# BaseBoard.net
KiCad netlist of a schematic drawn in EAGLE
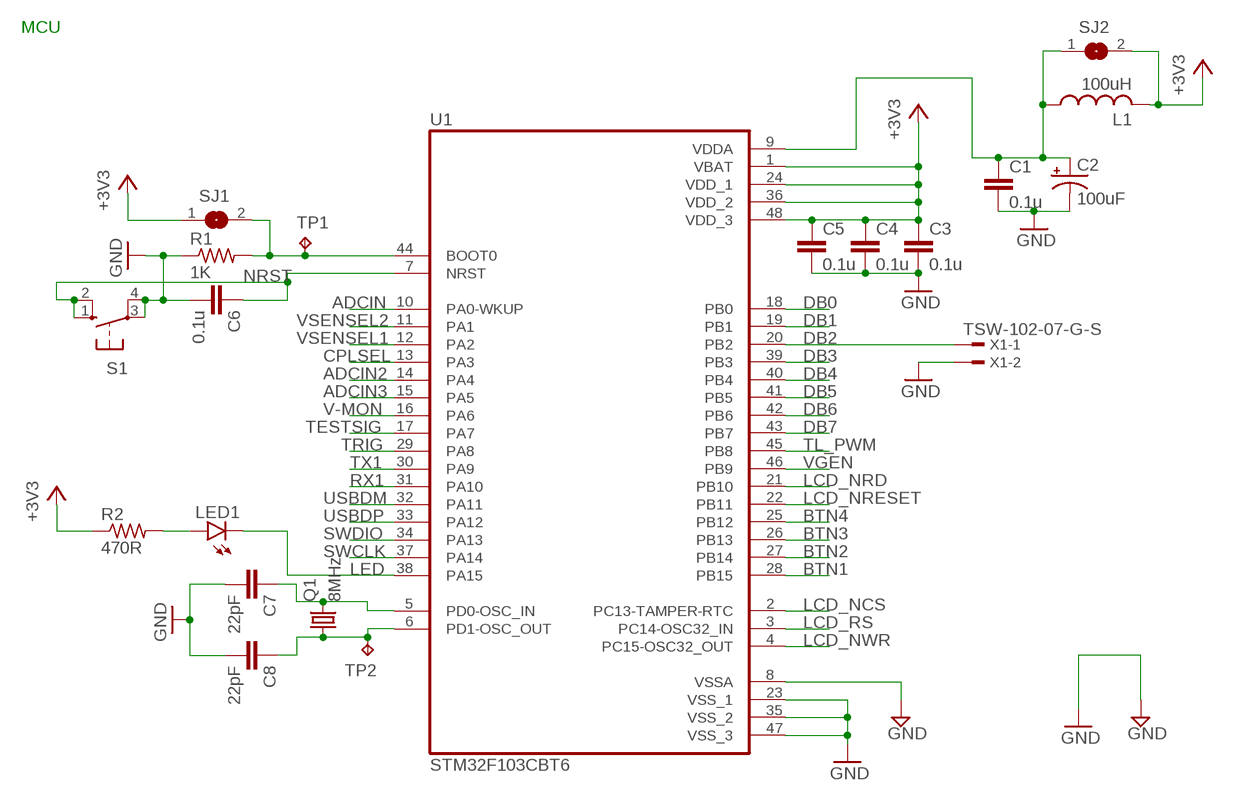
[diagram p0: schematic, sheet 1]
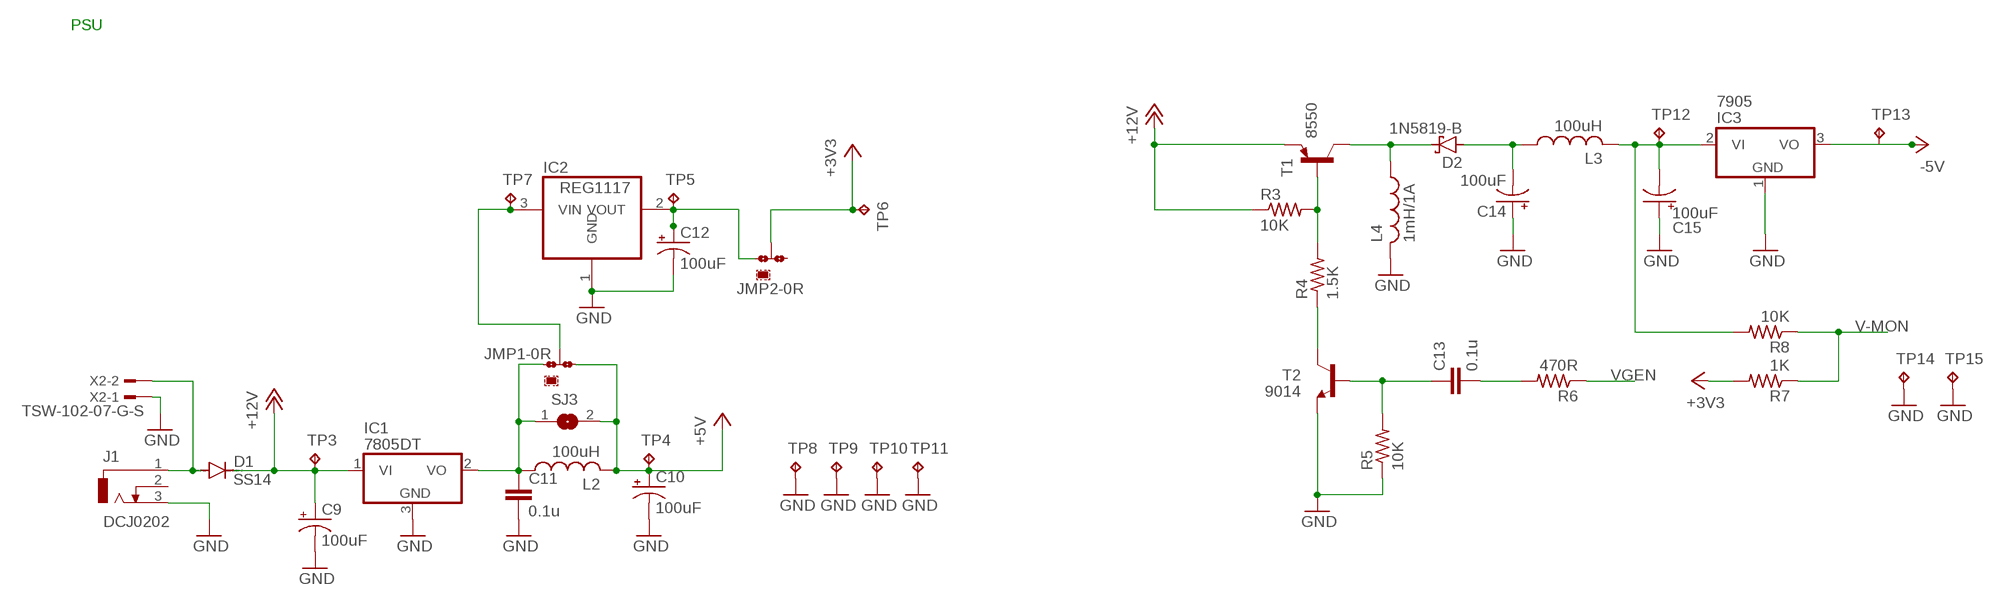
[diagram p1: schematic, sheet 2]
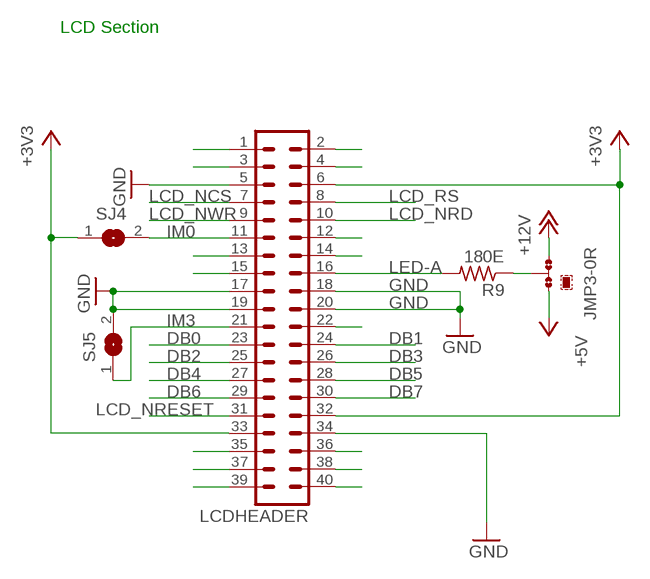
[diagram p2: schematic, sheet 3]
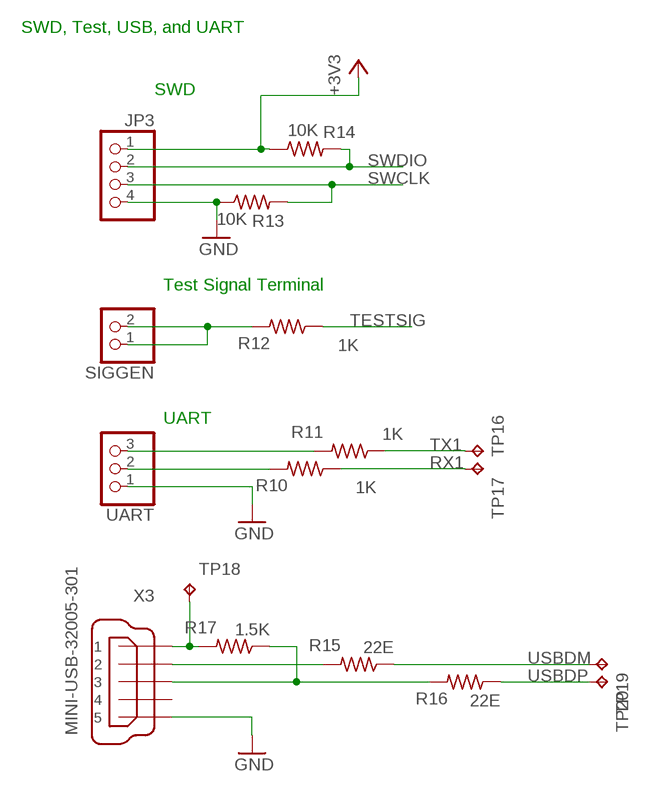
[diagram p3: schematic, sheet 4]
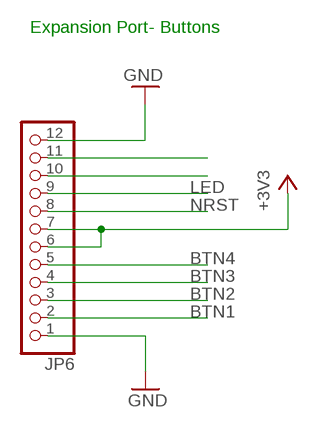
[diagram p4: schematic, sheet 5]
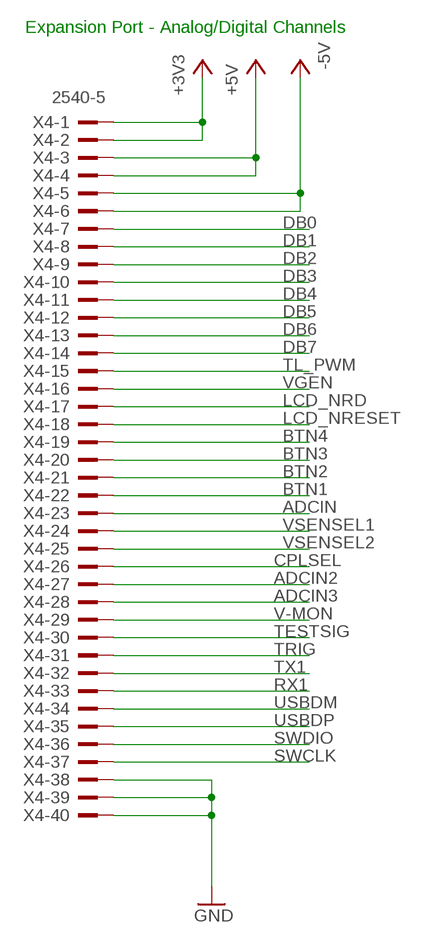
[diagram p5: schematic, sheet 6]

(export (version "E")
  (design (tool "Eeschema 10.0.6"))
  (components
    (comp (ref "X4")
      (value "2540-5")
      (footprint "eagle-import:PAK100_2500-5-40")
      (libsource (lib "eagle-import") (part "2540-5"))
    )
    (comp (ref "C1")
      (value "0.1u")
      (footprint "eagle-import:C1206")
      (libsource (lib "eagle-import") (part "C-EUC1206"))
    )
    (comp (ref "C2")
      (value "100uF")
      (footprint "eagle-import:CT6032")
      (libsource (lib "eagle-import") (part "CPOL-USCT6032"))
    )
    (comp (ref "C3")
      (value "0.1u")
      (footprint "eagle-import:C1206")
      (libsource (lib "eagle-import") (part "C-EUC1206"))
    )
    (comp (ref "C4")
      (value "0.1u")
      (footprint "eagle-import:C1206")
      (libsource (lib "eagle-import") (part "C-EUC1206"))
    )
    (comp (ref "C5")
      (value "0.1u")
      (footprint "eagle-import:C1206")
      (libsource (lib "eagle-import") (part "C-EUC1206"))
    )
    (comp (ref "C6")
      (value "0.1u")
      (footprint "eagle-import:C1206")
      (libsource (lib "eagle-import") (part "C-EUC1206"))
    )
    (comp (ref "C7")
      (value "22pF")
      (footprint "eagle-import:C1206")
      (libsource (lib "eagle-import") (part "C-EUC1206"))
    )
    (comp (ref "C8")
      (value "22pF")
      (footprint "eagle-import:C1206")
      (libsource (lib "eagle-import") (part "C-EUC1206"))
    )
    (comp (ref "L1")
      (value "100uH")
      (footprint "eagle-import:0204_5")
      (libsource (lib "eagle-import") (part "L-US0204/5"))
    )
    (comp (ref "LED1")
      (value "LEDCHIPLED_1206")
      (footprint "eagle-import:CHIPLED_1206")
      (libsource (lib "eagle-import") (part "LEDCHIPLED_1206"))
    )
    (comp (ref "Q1")
      (value "8MHz")
      (footprint "eagle-import:HC49_S")
      (libsource (lib "eagle-import") (part "CRYSTALHC49S"))
    )
    (comp (ref "R1")
      (value "1K")
      (footprint "eagle-import:R0805")
      (libsource (lib "eagle-import") (part "R-US_R0805"))
    )
    (comp (ref "R2")
      (value "470R")
      (footprint "eagle-import:R0805")
      (libsource (lib "eagle-import") (part "R-US_R0805"))
    )
    (comp (ref "S1")
      (value "10-XX")
      (footprint "eagle-import:B3F-10XX")
      (fields (field (name "MPN") "B3F-1000"))
      (libsource (lib "eagle-import") (part "10-XX"))
    )
    (comp (ref "SJ1")
      (value "SJW")
      (footprint "eagle-import:SJW")
      (libsource (lib "eagle-import") (part "SJW"))
    )
    (comp (ref "SJ2")
      (value "SJW")
      (footprint "eagle-import:SJW")
      (libsource (lib "eagle-import") (part "SJW"))
    )
    (comp (ref "TP1")
      (value "TPB1,27")
      (footprint "eagle-import:B1,27")
      (libsource (lib "eagle-import") (part "TPB1,27"))
    )
    (comp (ref "TP2")
      (value "TPB1,27")
      (footprint "eagle-import:B1,27")
      (libsource (lib "eagle-import") (part "TPB1,27"))
    )
    (comp (ref "U1")
      (value "STM32F103CBT6")
      (footprint "eagle-import:QFP50P900X900X160-48N")
      (fields (field (name "MF") "STMicroelectronics"))
      (libsource (lib "eagle-import") (part "STM32F103CBT6"))
    )
    (comp (ref "X1")
      (value "TSW-102-07-G-S")
      (footprint "eagle-import:TSW-102-XX-G-S")
      (fields (field (name "MF") "Samtec Inc."))
      (libsource (lib "eagle-import") (part "TSW-102--G-S07"))
    )
    (comp (ref "C9")
      (value "100uF")
      (footprint "eagle-import:CT6032")
      (libsource (lib "eagle-import") (part "CPOL-USCT6032"))
    )
    (comp (ref "C10")
      (value "100uF")
      (footprint "eagle-import:CT6032")
      (libsource (lib "eagle-import") (part "CPOL-USCT6032"))
    )
    (comp (ref "C11")
      (value "0.1u")
      (footprint "eagle-import:C1206")
      (libsource (lib "eagle-import") (part "C-EUC1206"))
    )
    (comp (ref "C12")
      (value "100uF")
      (footprint "eagle-import:CT6032")
      (libsource (lib "eagle-import") (part "CPOL-USCT6032"))
    )
    (comp (ref "C13")
      (value "0.1u")
      (footprint "eagle-import:C1206")
      (libsource (lib "eagle-import") (part "C-EUC1206"))
    )
    (comp (ref "C14")
      (value "100uF")
      (footprint "eagle-import:CT6032")
      (libsource (lib "eagle-import") (part "CPOL-USCT6032"))
    )
    (comp (ref "C15")
      (value "100uF")
      (footprint "eagle-import:CT6032")
      (libsource (lib "eagle-import") (part "CPOL-USCT6032"))
    )
    (comp (ref "D1")
      (value "SS14")
      (footprint "eagle-import:SMB")
      (libsource (lib "eagle-import") (part "ES2D"))
    )
    (comp (ref "D2")
      (value "1N5819-B")
      (footprint "eagle-import:DO41-7.6")
      (libsource (lib "eagle-import") (part "1N5819-B"))
    )
    (comp (ref "IC1")
      (value "7805DT")
      (footprint "eagle-import:TO252")
      (libsource (lib "eagle-import") (part "78DT05"))
    )
    (comp (ref "IC2")
      (value "REG1117")
      (footprint "eagle-import:SOT223")
      (libsource (lib "eagle-import") (part "REG1117"))
    )
    (comp (ref "IC3")
      (value "7905")
      (footprint "eagle-import:TO92")
      (libsource (lib "eagle-import") (part "79ZL05"))
    )
    (comp (ref "J1")
      (value "DCJ0202")
      (footprint "eagle-import:DCJ0202")
      (libsource (lib "eagle-import") (part "DCJ0202"))
    )
    (comp (ref "JMP1")
      (value "0R-JUMPA")
      (footprint "eagle-import:A0R-JMP")
      (libsource (lib "eagle-import") (part "0R-JUMPA"))
    )
    (comp (ref "JMP2")
      (value "0R-JUMPA")
      (footprint "eagle-import:A0R-JMP")
      (libsource (lib "eagle-import") (part "0R-JUMPA"))
    )
    (comp (ref "L2")
      (value "100uH")
      (footprint "eagle-import:0204_5")
      (libsource (lib "eagle-import") (part "L-US0204/5"))
    )
    (comp (ref "L3")
      (value "100uH")
      (footprint "eagle-import:0204_5")
      (libsource (lib "eagle-import") (part "L-US0204/5"))
    )
    (comp (ref "L4")
      (value "1mH/1A")
      (footprint "eagle-import:6000-XXXX-RC")
      (libsource (lib "eagle-import") (part "L-US6000-XXX-RC"))
    )
    (comp (ref "R3")
      (value "10K")
      (footprint "eagle-import:R0805")
      (libsource (lib "eagle-import") (part "R-US_R0805"))
    )
    (comp (ref "R4")
      (value "1.5K")
      (footprint "eagle-import:R0805")
      (libsource (lib "eagle-import") (part "R-US_R0805"))
    )
    (comp (ref "R5")
      (value "10K")
      (footprint "eagle-import:R0805")
      (libsource (lib "eagle-import") (part "R-US_R0805"))
    )
    (comp (ref "R6")
      (value "470R")
      (footprint "eagle-import:R0805")
      (libsource (lib "eagle-import") (part "R-US_R0805"))
    )
    (comp (ref "R7")
      (value "1K")
      (footprint "eagle-import:R0805")
      (libsource (lib "eagle-import") (part "R-US_R0805"))
    )
    (comp (ref "R8")
      (value "10K")
      (footprint "eagle-import:R0805")
      (libsource (lib "eagle-import") (part "R-US_R0805"))
    )
    (comp (ref "SJ3")
      (value "SJW")
      (footprint "eagle-import:SJW")
      (libsource (lib "eagle-import") (part "SJW"))
    )
    (comp (ref "T1")
      (value "8550")
      (footprint "eagle-import:TO92")
      (libsource (lib "eagle-import") (part "-PNP-TO92"))
    )
    (comp (ref "T2")
      (value "9014")
      (footprint "eagle-import:TO92")
      (libsource (lib "eagle-import") (part "-NPN-TO92"))
    )
    (comp (ref "TP3")
      (value "TPB1,27")
      (footprint "eagle-import:B1,27")
      (libsource (lib "eagle-import") (part "TPB1,27"))
    )
    (comp (ref "TP4")
      (value "TPB1,27")
      (footprint "eagle-import:B1,27")
      (libsource (lib "eagle-import") (part "TPB1,27"))
    )
    (comp (ref "TP5")
      (value "TPB1,27")
      (footprint "eagle-import:B1,27")
      (libsource (lib "eagle-import") (part "TPB1,27"))
    )
    (comp (ref "TP6")
      (value "TPB1,27")
      (footprint "eagle-import:B1,27")
      (libsource (lib "eagle-import") (part "TPB1,27"))
    )
    (comp (ref "TP7")
      (value "TPB1,27")
      (footprint "eagle-import:B1,27")
      (libsource (lib "eagle-import") (part "TPB1,27"))
    )
    (comp (ref "TP8")
      (value "TPB1,27")
      (footprint "eagle-import:B1,27")
      (libsource (lib "eagle-import") (part "TPB1,27"))
    )
    (comp (ref "TP9")
      (value "TPB1,27")
      (footprint "eagle-import:B1,27")
      (libsource (lib "eagle-import") (part "TPB1,27"))
    )
    (comp (ref "TP10")
      (value "TPB1,27")
      (footprint "eagle-import:B1,27")
      (libsource (lib "eagle-import") (part "TPB1,27"))
    )
    (comp (ref "TP11")
      (value "TPB1,27")
      (footprint "eagle-import:B1,27")
      (libsource (lib "eagle-import") (part "TPB1,27"))
    )
    (comp (ref "TP12")
      (value "TPB1,27")
      (footprint "eagle-import:B1,27")
      (libsource (lib "eagle-import") (part "TPB1,27"))
    )
    (comp (ref "TP13")
      (value "TPB1,27")
      (footprint "eagle-import:B1,27")
      (libsource (lib "eagle-import") (part "TPB1,27"))
    )
    (comp (ref "TP14")
      (value "TPB1,27")
      (footprint "eagle-import:B1,27")
      (libsource (lib "eagle-import") (part "TPB1,27"))
    )
    (comp (ref "TP15")
      (value "TPB1,27")
      (footprint "eagle-import:B1,27")
      (libsource (lib "eagle-import") (part "TPB1,27"))
    )
    (comp (ref "X2")
      (value "TSW-102-07-G-S")
      (footprint "eagle-import:TSW-102-XX-G-S")
      (fields (field (name "MF") "Samtec Inc."))
      (libsource (lib "eagle-import") (part "TSW-102--G-S07"))
    )
    (comp (ref "JMP3")
      (value "0R-JUMPA")
      (footprint "eagle-import:A0R-JMP")
      (libsource (lib "eagle-import") (part "0R-JUMPA"))
    )
    (comp (ref "LCDHEADER")
      (value "MA20-2")
      (footprint "eagle-import:MA20-2")
      (libsource (lib "eagle-import") (part "MA20-2"))
    )
    (comp (ref "R9")
      (value "180E")
      (footprint "eagle-import:R0805")
      (libsource (lib "eagle-import") (part "R-US_R0805"))
    )
    (comp (ref "SJ4") (value "SJ") (footprint "eagle-import:SJ") (libsource (lib "eagle-import") (part "SJ")))
    (comp (ref "SJ5") (value "SJ") (footprint "eagle-import:SJ") (libsource (lib "eagle-import") (part "SJ")))
    (comp (ref "JP3")
      (value "PINHD-1X4")
      (footprint "eagle-import:1X04")
      (libsource (lib "eagle-import") (part "PINHD-1X4"))
    )
    (comp (ref "R10")
      (value "1K")
      (footprint "eagle-import:R0805")
      (libsource (lib "eagle-import") (part "R-US_R0805"))
    )
    (comp (ref "R11")
      (value "1K")
      (footprint "eagle-import:R0805")
      (libsource (lib "eagle-import") (part "R-US_R0805"))
    )
    (comp (ref "R12")
      (value "1K")
      (footprint "eagle-import:R0805")
      (libsource (lib "eagle-import") (part "R-US_R0805"))
    )
    (comp (ref "R13")
      (value "10K")
      (footprint "eagle-import:R0805")
      (libsource (lib "eagle-import") (part "R-US_R0805"))
    )
    (comp (ref "R14")
      (value "10K")
      (footprint "eagle-import:R0805")
      (libsource (lib "eagle-import") (part "R-US_R0805"))
    )
    (comp (ref "R15")
      (value "22E")
      (footprint "eagle-import:R0805")
      (libsource (lib "eagle-import") (part "R-US_R0805"))
    )
    (comp (ref "R16")
      (value "22E")
      (footprint "eagle-import:R0805")
      (libsource (lib "eagle-import") (part "R-US_R0805"))
    )
    (comp (ref "R17")
      (value "1.5K")
      (footprint "eagle-import:R0805")
      (libsource (lib "eagle-import") (part "R-US_R0805"))
    )
    (comp (ref "SIGGEN")
      (value "PINHD-1X2")
      (footprint "eagle-import:1X02")
      (libsource (lib "eagle-import") (part "PINHD-1X2"))
    )
    (comp (ref "TP16")
      (value "TPB1,27")
      (footprint "eagle-import:B1,27")
      (libsource (lib "eagle-import") (part "TPB1,27"))
    )
    (comp (ref "TP17")
      (value "TPB1,27")
      (footprint "eagle-import:B1,27")
      (libsource (lib "eagle-import") (part "TPB1,27"))
    )
    (comp (ref "TP18")
      (value "TPB1,27")
      (footprint "eagle-import:B1,27")
      (libsource (lib "eagle-import") (part "TPB1,27"))
    )
    (comp (ref "TP19")
      (value "TPB1,27")
      (footprint "eagle-import:B1,27")
      (libsource (lib "eagle-import") (part "TPB1,27"))
    )
    (comp (ref "TP20")
      (value "TPB1,27")
      (footprint "eagle-import:B1,27")
      (libsource (lib "eagle-import") (part "TPB1,27"))
    )
    (comp (ref "UART")
      (value "PINHD-1X3")
      (footprint "eagle-import:1X03")
      (libsource (lib "eagle-import") (part "PINHD-1X3"))
    )
    (comp (ref "X3")
      (value "MINI-USB-32005-301")
      (footprint "eagle-import:32005-301")
      (libsource (lib "eagle-import") (part "MINI-USB-32005-301"))
    )
    (comp (ref "JP6")
      (value "PINHD-1X12")
      (footprint "eagle-import:1X12")
      (libsource (lib "eagle-import") (part "PINHD-1X12"))
    )
  )
  (nets
    (net (code "1") (name "+3V3") (class "Default")
      (node (ref "C3") (pin "1") (pinfunction "1_1") (pintype "passive"))
      (node (ref "C4") (pin "1") (pinfunction "1_1") (pintype "passive"))
      (node (ref "C5") (pin "1") (pinfunction "1_1") (pintype "passive"))
      (node (ref "JMP2") (pin "2") (pinfunction "2_2") (pintype "passive"))
      (node (ref "JP3") (pin "1") (pinfunction "1_1") (pintype "passive"))
      (node (ref "JP6") (pin "6") (pinfunction "6_6") (pintype "passive"))
      (node (ref "JP6") (pin "7") (pinfunction "7_7") (pintype "passive"))
      (node (ref "L1") (pin "2") (pinfunction "2_2") (pintype "passive"))
      (node (ref "LCDHEADER") (pin "32") (pinfunction "32_32") (pintype "passive"))
      (node (ref "LCDHEADER") (pin "33") (pinfunction "33_33") (pintype "passive"))
      (node (ref "LCDHEADER") (pin "6") (pinfunction "6_6") (pintype "passive"))
      (node (ref "R14") (pin "1") (pinfunction "1_1") (pintype "passive"))
      (node (ref "R2") (pin "1") (pinfunction "1_1") (pintype "passive"))
      (node (ref "R7") (pin "2") (pinfunction "2_2") (pintype "passive"))
      (node (ref "SJ1") (pin "1") (pinfunction "1_1") (pintype "passive"))
      (node (ref "SJ2") (pin "2") (pinfunction "2_2") (pintype "passive"))
      (node (ref "SJ4") (pin "1") (pinfunction "1_1") (pintype "passive"))
      (node (ref "TP6") (pin "TP") (pinfunction "TP_TP") (pintype "input"))
      (node (ref "U1") (pin "1") (pinfunction "VBAT_1") (pintype "power_in"))
      (node (ref "U1") (pin "24") (pinfunction "VDD_1_24") (pintype "power_in"))
      (node (ref "U1") (pin "36") (pinfunction "VDD_2_36") (pintype "power_in"))
      (node (ref "U1") (pin "48") (pinfunction "VDD_3_48") (pintype "power_in"))
      (node (ref "X4") (pin "1") (pinfunction "KL_1") (pintype "passive"))
      (node (ref "X4") (pin "2") (pinfunction "KL_2") (pintype "passive"))
    )
    (net (code "2") (name "+5V") (class "Default")
      (node (ref "C10") (pin "+") (pinfunction "+_+") (pintype "passive"))
      (node (ref "JMP1") (pin "3") (pinfunction "3_3") (pintype "passive"))
      (node (ref "JMP3") (pin "1") (pinfunction "1_1") (pintype "passive"))
      (node (ref "L2") (pin "2") (pinfunction "2_2") (pintype "passive"))
      (node (ref "SJ3") (pin "2") (pinfunction "2_2") (pintype "passive"))
      (node (ref "TP4") (pin "TP") (pinfunction "TP_TP") (pintype "input"))
      (node (ref "X4") (pin "3") (pinfunction "KL_3") (pintype "passive"))
      (node (ref "X4") (pin "4") (pinfunction "KL_4") (pintype "passive"))
    )
    (net (code "3") (name "+12V") (class "Default")
      (node (ref "C9") (pin "+") (pinfunction "+_+") (pintype "passive"))
      (node (ref "D1") (pin "C") (pinfunction "C_C") (pintype "passive"))
      (node (ref "IC1") (pin "1") (pinfunction "VI_1") (pintype "input"))
      (node (ref "JMP3") (pin "3") (pinfunction "3_3") (pintype "passive"))
      (node (ref "R3") (pin "1") (pinfunction "1_1") (pintype "passive"))
      (node (ref "T1") (pin "1") (pinfunction "E_1") (pintype "passive"))
      (node (ref "TP3") (pin "TP") (pinfunction "TP_TP") (pintype "input"))
    )
    (net (code "4") (name "-5V") (class "Default")
      (node (ref "IC3") (pin "3") (pinfunction "VO_3") (pintype "passive"))
      (node (ref "TP13") (pin "TP") (pinfunction "TP_TP") (pintype "input"))
      (node (ref "X4") (pin "5") (pinfunction "KL_5") (pintype "passive"))
      (node (ref "X4") (pin "6") (pinfunction "KL_6") (pintype "passive"))
    )
    (net (code "5") (name "ADCIN") (class "Default")
      (node (ref "U1") (pin "10") (pinfunction "PA0-WKUP_10") (pintype "bidirectional"))
      (node (ref "X4") (pin "23") (pinfunction "KL_23") (pintype "passive"))
    )
    (net (code "6") (name "ADCIN2") (class "Default")
      (node (ref "U1") (pin "14") (pinfunction "PA4_14") (pintype "bidirectional"))
      (node (ref "X4") (pin "27") (pinfunction "KL_27") (pintype "passive"))
    )
    (net (code "7") (name "ADCIN3") (class "Default")
      (node (ref "U1") (pin "15") (pinfunction "PA5_15") (pintype "bidirectional"))
      (node (ref "X4") (pin "28") (pinfunction "KL_28") (pintype "passive"))
    )
    (net (code "8") (name "BTN1") (class "Default")
      (node (ref "JP6") (pin "2") (pinfunction "2_2") (pintype "passive"))
      (node (ref "U1") (pin "28") (pinfunction "PB15_28") (pintype "bidirectional"))
      (node (ref "X4") (pin "22") (pinfunction "KL_22") (pintype "passive"))
    )
    (net (code "9") (name "BTN2") (class "Default")
      (node (ref "JP6") (pin "3") (pinfunction "3_3") (pintype "passive"))
      (node (ref "U1") (pin "27") (pinfunction "PB14_27") (pintype "bidirectional"))
      (node (ref "X4") (pin "21") (pinfunction "KL_21") (pintype "passive"))
    )
    (net (code "10") (name "BTN3") (class "Default")
      (node (ref "JP6") (pin "4") (pinfunction "4_4") (pintype "passive"))
      (node (ref "U1") (pin "26") (pinfunction "PB13_26") (pintype "bidirectional"))
      (node (ref "X4") (pin "20") (pinfunction "KL_20") (pintype "passive"))
    )
    (net (code "11") (name "BTN4") (class "Default")
      (node (ref "JP6") (pin "5") (pinfunction "5_5") (pintype "passive"))
      (node (ref "U1") (pin "25") (pinfunction "PB12_25") (pintype "bidirectional"))
      (node (ref "X4") (pin "19") (pinfunction "KL_19") (pintype "passive"))
    )
    (net (code "12") (name "CPLSEL") (class "Default")
      (node (ref "U1") (pin "13") (pinfunction "PA3_13") (pintype "bidirectional"))
      (node (ref "X4") (pin "26") (pinfunction "KL_26") (pintype "passive"))
    )
    (net (code "13") (name "DB0") (class "Default")
      (node (ref "LCDHEADER") (pin "23") (pinfunction "23_23") (pintype "passive"))
      (node (ref "U1") (pin "18") (pinfunction "PB0_18") (pintype "bidirectional"))
      (node (ref "X4") (pin "7") (pinfunction "KL_7") (pintype "passive"))
    )
    (net (code "14") (name "DB1") (class "Default")
      (node (ref "LCDHEADER") (pin "24") (pinfunction "24_24") (pintype "passive"))
      (node (ref "U1") (pin "19") (pinfunction "PB1_19") (pintype "bidirectional"))
      (node (ref "X4") (pin "8") (pinfunction "KL_8") (pintype "passive"))
    )
    (net (code "15") (name "DB2") (class "Default")
      (node (ref "LCDHEADER") (pin "25") (pinfunction "25_25") (pintype "passive"))
      (node (ref "U1") (pin "20") (pinfunction "PB2_20") (pintype "bidirectional"))
      (node (ref "X1") (pin "1") (pinfunction "1_1") (pintype "passive"))
      (node (ref "X4") (pin "9") (pinfunction "KL_9") (pintype "passive"))
    )
    (net (code "16") (name "DB3") (class "Default")
      (node (ref "LCDHEADER") (pin "26") (pinfunction "26_26") (pintype "passive"))
      (node (ref "U1") (pin "39") (pinfunction "PB3_39") (pintype "bidirectional"))
      (node (ref "X4") (pin "10") (pinfunction "KL_10") (pintype "passive"))
    )
    (net (code "17") (name "DB4") (class "Default")
      (node (ref "LCDHEADER") (pin "27") (pinfunction "27_27") (pintype "passive"))
      (node (ref "U1") (pin "40") (pinfunction "PB4_40") (pintype "bidirectional"))
      (node (ref "X4") (pin "11") (pinfunction "KL_11") (pintype "passive"))
    )
    (net (code "18") (name "DB5") (class "Default")
      (node (ref "LCDHEADER") (pin "28") (pinfunction "28_28") (pintype "passive"))
      (node (ref "U1") (pin "41") (pinfunction "PB5_41") (pintype "bidirectional"))
      (node (ref "X4") (pin "12") (pinfunction "KL_12") (pintype "passive"))
    )
    (net (code "19") (name "DB6") (class "Default")
      (node (ref "LCDHEADER") (pin "29") (pinfunction "29_29") (pintype "passive"))
      (node (ref "U1") (pin "42") (pinfunction "PB6_42") (pintype "bidirectional"))
      (node (ref "X4") (pin "13") (pinfunction "KL_13") (pintype "passive"))
    )
    (net (code "20") (name "DB7") (class "Default")
      (node (ref "LCDHEADER") (pin "30") (pinfunction "30_30") (pintype "passive"))
      (node (ref "U1") (pin "43") (pinfunction "PB7_43") (pintype "bidirectional"))
      (node (ref "X4") (pin "14") (pinfunction "KL_14") (pintype "passive"))
    )
    (net (code "21") (name "GND") (class "Default")
      (node (ref "C1") (pin "2") (pinfunction "2_2") (pintype "passive"))
      (node (ref "C10") (pin "-") (pinfunction "-_-") (pintype "passive"))
      (node (ref "C11") (pin "2") (pinfunction "2_2") (pintype "passive"))
      (node (ref "C12") (pin "-") (pinfunction "-_-") (pintype "passive"))
      (node (ref "C14") (pin "+") (pinfunction "+_+") (pintype "passive"))
      (node (ref "C15") (pin "+") (pinfunction "+_+") (pintype "passive"))
      (node (ref "C2") (pin "-") (pinfunction "-_-") (pintype "passive"))
      (node (ref "C3") (pin "2") (pinfunction "2_2") (pintype "passive"))
      (node (ref "C4") (pin "2") (pinfunction "2_2") (pintype "passive"))
      (node (ref "C5") (pin "2") (pinfunction "2_2") (pintype "passive"))
      (node (ref "C6") (pin "2") (pinfunction "2_2") (pintype "passive"))
      (node (ref "C7") (pin "2") (pinfunction "2_2") (pintype "passive"))
      (node (ref "C8") (pin "2") (pinfunction "2_2") (pintype "passive"))
      (node (ref "C9") (pin "-") (pinfunction "-_-") (pintype "passive"))
      (node (ref "IC1") (pin "3") (pinfunction "GND_3") (pintype "passive"))
      (node (ref "IC2") (pin "1") (pinfunction "GND_1") (pintype "power_in"))
      (node (ref "IC3") (pin "1") (pinfunction "GND_1") (pintype "passive"))
      (node (ref "J1") (pin "3") (pinfunction "3_3") (pintype "passive"))
      (node (ref "JP3") (pin "4") (pinfunction "4_4") (pintype "passive"))
      (node (ref "JP6") (pin "1") (pinfunction "1_1") (pintype "passive"))
      (node (ref "JP6") (pin "12") (pinfunction "12_12") (pintype "passive"))
      (node (ref "L4") (pin "2") (pinfunction "2_2") (pintype "passive"))
      (node (ref "LCDHEADER") (pin "17") (pinfunction "17_17") (pintype "passive"))
      (node (ref "LCDHEADER") (pin "18") (pinfunction "18_18") (pintype "passive"))
      (node (ref "LCDHEADER") (pin "19") (pinfunction "19_19") (pintype "passive"))
      (node (ref "LCDHEADER") (pin "20") (pinfunction "20_20") (pintype "passive"))
      (node (ref "LCDHEADER") (pin "34") (pinfunction "34_34") (pintype "passive"))
      (node (ref "LCDHEADER") (pin "5") (pinfunction "5_5") (pintype "passive"))
      (node (ref "R1") (pin "1") (pinfunction "1_1") (pintype "passive"))
      (node (ref "R13") (pin "1") (pinfunction "1_1") (pintype "passive"))
      (node (ref "R5") (pin "1") (pinfunction "1_1") (pintype "passive"))
      (node (ref "S1") (pin "3") (pinfunction "P_3") (pintype "passive"))
      (node (ref "S1") (pin "4") (pinfunction "P1_4") (pintype "passive"))
      (node (ref "SJ5") (pin "2") (pinfunction "2_2") (pintype "passive"))
      (node (ref "T2") (pin "1") (pinfunction "E_1") (pintype "passive"))
      (node (ref "TP10") (pin "TP") (pinfunction "TP_TP") (pintype "input"))
      (node (ref "TP11") (pin "TP") (pinfunction "TP_TP") (pintype "input"))
      (node (ref "TP14") (pin "TP") (pinfunction "TP_TP") (pintype "input"))
      (node (ref "TP15") (pin "TP") (pinfunction "TP_TP") (pintype "input"))
      (node (ref "TP8") (pin "TP") (pinfunction "TP_TP") (pintype "input"))
      (node (ref "TP9") (pin "TP") (pinfunction "TP_TP") (pintype "input"))
      (node (ref "U1") (pin "23") (pinfunction "VSS_1_23") (pintype "power_in"))
      (node (ref "U1") (pin "35") (pinfunction "VSS_2_35") (pintype "power_in"))
      (node (ref "U1") (pin "47") (pinfunction "VSS_3_47") (pintype "power_in"))
      (node (ref "U1") (pin "8") (pinfunction "VSSA_8") (pintype "power_in"))
      (node (ref "UART") (pin "1") (pinfunction "1_1") (pintype "passive"))
      (node (ref "X1") (pin "2") (pinfunction "1_2") (pintype "passive"))
      (node (ref "X2") (pin "1") (pinfunction "1_1") (pintype "passive"))
      (node (ref "X3") (pin "5") (pinfunction "5_5") (pintype "passive"))
      (node (ref "X4") (pin "38") (pinfunction "KL_38") (pintype "passive"))
      (node (ref "X4") (pin "39") (pinfunction "KL_39") (pintype "passive"))
      (node (ref "X4") (pin "40") (pinfunction "KL_40") (pintype "passive"))
    )
    (net (code "22") (name "IM0") (class "Default")
      (node (ref "LCDHEADER") (pin "11") (pinfunction "11_11") (pintype "passive"))
      (node (ref "SJ4") (pin "2") (pinfunction "2_2") (pintype "passive"))
    )
    (net (code "23") (name "IM3") (class "Default")
      (node (ref "LCDHEADER") (pin "21") (pinfunction "21_21") (pintype "passive"))
      (node (ref "SJ5") (pin "1") (pinfunction "1_1") (pintype "passive"))
    )
    (net (code "24") (name "LCD_NCS") (class "Default")
      (node (ref "LCDHEADER") (pin "7") (pinfunction "7_7") (pintype "passive"))
      (node (ref "U1") (pin "2") (pinfunction "PC13-TAMPER-RTC_2") (pintype "bidirectional"))
    )
    (net (code "25") (name "LCD_NRD") (class "Default")
      (node (ref "LCDHEADER") (pin "10") (pinfunction "10_10") (pintype "passive"))
      (node (ref "U1") (pin "21") (pinfunction "PB10_21") (pintype "bidirectional"))
      (node (ref "X4") (pin "17") (pinfunction "KL_17") (pintype "passive"))
    )
    (net (code "26") (name "LCD_NRESET") (class "Default")
      (node (ref "LCDHEADER") (pin "31") (pinfunction "31_31") (pintype "passive"))
      (node (ref "U1") (pin "22") (pinfunction "PB11_22") (pintype "bidirectional"))
      (node (ref "X4") (pin "18") (pinfunction "KL_18") (pintype "passive"))
    )
    (net (code "27") (name "LCD_NWR") (class "Default")
      (node (ref "LCDHEADER") (pin "9") (pinfunction "9_9") (pintype "passive"))
      (node (ref "U1") (pin "4") (pinfunction "PC15-OSC32_OUT_4") (pintype "bidirectional"))
    )
    (net (code "28") (name "LCD_RS") (class "Default")
      (node (ref "LCDHEADER") (pin "8") (pinfunction "8_8") (pintype "passive"))
      (node (ref "U1") (pin "3") (pinfunction "PC14-OSC32_IN_3") (pintype "bidirectional"))
    )
    (net (code "29") (name "LED") (class "Default")
      (node (ref "JP6") (pin "9") (pinfunction "9_9") (pintype "passive"))
      (node (ref "LED1") (pin "C") (pinfunction "C_C") (pintype "passive"))
      (node (ref "U1") (pin "38") (pinfunction "PA15_38") (pintype "bidirectional"))
    )
    (net (code "30") (name "LED-A") (class "Default")
      (node (ref "LCDHEADER") (pin "16") (pinfunction "16_16") (pintype "passive"))
      (node (ref "R9") (pin "2") (pinfunction "2_2") (pintype "passive"))
    )
    (net (code "31") (name "NRST") (class "Default")
      (node (ref "C6") (pin "1") (pinfunction "1_1") (pintype "passive"))
      (node (ref "JP6") (pin "8") (pinfunction "8_8") (pintype "passive"))
      (node (ref "S1") (pin "1") (pinfunction "S_1") (pintype "passive"))
      (node (ref "S1") (pin "2") (pinfunction "S1_2") (pintype "passive"))
      (node (ref "U1") (pin "7") (pinfunction "NRST_7") (pintype "bidirectional"))
    )
    (net (code "32") (name "Net-(C13-Pad2)") (class "Default")
      (node (ref "C13") (pin "2") (pinfunction "2_2") (pintype "passive"))
      (node (ref "R6") (pin "2") (pinfunction "2_2") (pintype "passive"))
    )
    (net (code "33") (name "Net-(C14-Pad-)") (class "Default")
      (node (ref "C14") (pin "-") (pinfunction "-_-") (pintype "passive"))
      (node (ref "D2") (pin "A") (pinfunction "A_A") (pintype "passive"))
      (node (ref "L3") (pin "1") (pinfunction "1_1") (pintype "passive"))
    )
    (net (code "34") (name "Net-(IC1-VO)") (class "Default")
      (node (ref "C11") (pin "1") (pinfunction "1_1") (pintype "passive"))
      (node (ref "IC1") (pin "2") (pinfunction "VO_2") (pintype "passive"))
      (node (ref "JMP1") (pin "1") (pinfunction "1_1") (pintype "passive"))
      (node (ref "L2") (pin "1") (pinfunction "1_1") (pintype "passive"))
      (node (ref "SJ3") (pin "1") (pinfunction "1_1") (pintype "passive"))
    )
    (net (code "35") (name "Net-(IC2-VIN)") (class "Default")
      (node (ref "IC2") (pin "3") (pinfunction "VIN_3") (pintype "input"))
      (node (ref "JMP1") (pin "2") (pinfunction "2_2") (pintype "passive"))
      (node (ref "TP7") (pin "TP") (pinfunction "TP_TP") (pintype "input"))
    )
    (net (code "36") (name "Net-(IC2-VOUT)") (class "Default")
      (node (ref "C12") (pin "+") (pinfunction "+_+") (pintype "passive"))
      (node (ref "IC2") (pin "2") (pinfunction "VOUT_2") (pintype "output"))
      (node (ref "JMP2") (pin "1") (pinfunction "1_1") (pintype "passive"))
      (node (ref "TP5") (pin "TP") (pinfunction "TP_TP") (pintype "input"))
    )
    (net (code "37") (name "Net-(IC3-VI)") (class "Default")
      (node (ref "C15") (pin "-") (pinfunction "-_-") (pintype "passive"))
      (node (ref "IC3") (pin "2") (pinfunction "VI_2") (pintype "input"))
      (node (ref "L3") (pin "2") (pinfunction "2_2") (pintype "passive"))
      (node (ref "R8") (pin "2") (pinfunction "2_2") (pintype "passive"))
      (node (ref "TP12") (pin "TP") (pinfunction "TP_TP") (pintype "input"))
    )
    (net (code "38") (name "Net-(JMP3-Pad2)") (class "Default")
      (node (ref "JMP3") (pin "2") (pinfunction "2_2") (pintype "passive"))
      (node (ref "R9") (pin "1") (pinfunction "1_1") (pintype "passive"))
    )
    (net (code "39") (name "Net-(LED1-PadA)") (class "Default")
      (node (ref "LED1") (pin "A") (pinfunction "A_A") (pintype "passive"))
      (node (ref "R2") (pin "2") (pinfunction "2_2") (pintype "passive"))
    )
    (net (code "40") (name "Net-(R10-Pad2)") (class "Default")
      (node (ref "R10") (pin "2") (pinfunction "2_2") (pintype "passive"))
      (node (ref "UART") (pin "2") (pinfunction "2_2") (pintype "passive"))
    )
    (net (code "41") (name "Net-(R11-Pad2)") (class "Default")
      (node (ref "R11") (pin "2") (pinfunction "2_2") (pintype "passive"))
      (node (ref "UART") (pin "3") (pinfunction "3_3") (pintype "passive"))
    )
    (net (code "42") (name "Net-(R12-Pad2)") (class "Default")
      (node (ref "R12") (pin "2") (pinfunction "2_2") (pintype "passive"))
      (node (ref "SIGGEN") (pin "1") (pinfunction "1_1") (pintype "passive"))
      (node (ref "SIGGEN") (pin "2") (pinfunction "2_2") (pintype "passive"))
    )
    (net (code "43") (name "Net-(R15-Pad2)") (class "Default")
      (node (ref "R15") (pin "2") (pinfunction "2_2") (pintype "passive"))
      (node (ref "X3") (pin "2") (pinfunction "2_2") (pintype "passive"))
    )
    (net (code "44") (name "Net-(R16-Pad2)") (class "Default")
      (node (ref "R16") (pin "2") (pinfunction "2_2") (pintype "passive"))
      (node (ref "R17") (pin "1") (pinfunction "1_1") (pintype "passive"))
      (node (ref "X3") (pin "3") (pinfunction "3_3") (pintype "passive"))
    )
    (net (code "45") (name "Net-(R17-Pad2)") (class "Default")
      (node (ref "R17") (pin "2") (pinfunction "2_2") (pintype "passive"))
      (node (ref "TP18") (pin "TP") (pinfunction "TP_TP") (pintype "input"))
      (node (ref "X3") (pin "1") (pinfunction "1_1") (pintype "passive"))
    )
    (net (code "46") (name "Net-(T1-B)") (class "Default")
      (node (ref "R3") (pin "2") (pinfunction "2_2") (pintype "passive"))
      (node (ref "R4") (pin "2") (pinfunction "2_2") (pintype "passive"))
      (node (ref "T1") (pin "2") (pinfunction "B_2") (pintype "passive"))
    )
    (net (code "47") (name "Net-(T1-C)") (class "Default")
      (node (ref "D2") (pin "C") (pinfunction "C_C") (pintype "passive"))
      (node (ref "L4") (pin "1") (pinfunction "1_1") (pintype "passive"))
      (node (ref "T1") (pin "3") (pinfunction "C_3") (pintype "passive"))
    )
    (net (code "48") (name "Net-(T2-B)") (class "Default")
      (node (ref "C13") (pin "1") (pinfunction "1_1") (pintype "passive"))
      (node (ref "R5") (pin "2") (pinfunction "2_2") (pintype "passive"))
      (node (ref "T2") (pin "2") (pinfunction "B_2") (pintype "passive"))
    )
    (net (code "49") (name "Net-(T2-C)") (class "Default")
      (node (ref "R4") (pin "1") (pinfunction "1_1") (pintype "passive"))
      (node (ref "T2") (pin "3") (pinfunction "C_3") (pintype "passive"))
    )
    (net (code "50") (name "Net-(U1-BOOT0)") (class "Default")
      (node (ref "R1") (pin "2") (pinfunction "2_2") (pintype "passive"))
      (node (ref "SJ1") (pin "2") (pinfunction "2_2") (pintype "passive"))
      (node (ref "TP1") (pin "TP") (pinfunction "TP_TP") (pintype "input"))
      (node (ref "U1") (pin "44") (pinfunction "BOOT0_44") (pintype "input"))
    )
    (net (code "51") (name "Net-(U1-PD0-OSC_IN)") (class "Default")
      (node (ref "C7") (pin "1") (pinfunction "1_1") (pintype "passive"))
      (node (ref "Q1") (pin "2") (pinfunction "2_2") (pintype "passive"))
      (node (ref "U1") (pin "5") (pinfunction "PD0-OSC_IN_5") (pintype "bidirectional"))
    )
    (net (code "52") (name "Net-(U1-PD1-OSC_OUT)") (class "Default")
      (node (ref "C8") (pin "1") (pinfunction "1_1") (pintype "passive"))
      (node (ref "Q1") (pin "1") (pinfunction "1_1") (pintype "passive"))
      (node (ref "TP2") (pin "TP") (pinfunction "TP_TP") (pintype "input"))
      (node (ref "U1") (pin "6") (pinfunction "PD1-OSC_OUT_6") (pintype "bidirectional"))
    )
    (net (code "53") (name "Net-(U1-VDDA)") (class "Default")
      (node (ref "C1") (pin "1") (pinfunction "1_1") (pintype "passive"))
      (node (ref "C2") (pin "+") (pinfunction "+_+") (pintype "passive"))
      (node (ref "L1") (pin "1") (pinfunction "1_1") (pintype "passive"))
      (node (ref "SJ2") (pin "1") (pinfunction "1_1") (pintype "passive"))
      (node (ref "U1") (pin "9") (pinfunction "VDDA_9") (pintype "power_in"))
    )
    (net (code "54") (name "Net-(X2B-1)") (class "Default")
      (node (ref "D1") (pin "A") (pinfunction "A_A") (pintype "passive"))
      (node (ref "J1") (pin "1") (pinfunction "1_1") (pintype "passive"))
      (node (ref "X2") (pin "2") (pinfunction "1_2") (pintype "passive"))
    )
    (net (code "55") (name "RX1") (class "Default")
      (node (ref "R10") (pin "1") (pinfunction "1_1") (pintype "passive"))
      (node (ref "TP17") (pin "TP") (pinfunction "TP_TP") (pintype "input"))
      (node (ref "U1") (pin "31") (pinfunction "PA10_31") (pintype "bidirectional"))
      (node (ref "X4") (pin "33") (pinfunction "KL_33") (pintype "passive"))
    )
    (net (code "56") (name "SWCLK") (class "Default")
      (node (ref "JP3") (pin "3") (pinfunction "3_3") (pintype "passive"))
      (node (ref "R13") (pin "2") (pinfunction "2_2") (pintype "passive"))
      (node (ref "U1") (pin "37") (pinfunction "PA14_37") (pintype "bidirectional"))
      (node (ref "X4") (pin "37") (pinfunction "KL_37") (pintype "passive"))
    )
    (net (code "57") (name "SWDIO") (class "Default")
      (node (ref "JP3") (pin "2") (pinfunction "2_2") (pintype "passive"))
      (node (ref "R14") (pin "2") (pinfunction "2_2") (pintype "passive"))
      (node (ref "U1") (pin "34") (pinfunction "PA13_34") (pintype "bidirectional"))
      (node (ref "X4") (pin "36") (pinfunction "KL_36") (pintype "passive"))
    )
    (net (code "58") (name "TESTSIG") (class "Default")
      (node (ref "R12") (pin "1") (pinfunction "1_1") (pintype "passive"))
      (node (ref "U1") (pin "17") (pinfunction "PA7_17") (pintype "bidirectional"))
      (node (ref "X4") (pin "30") (pinfunction "KL_30") (pintype "passive"))
    )
    (net (code "59") (name "TL_PWM") (class "Default")
      (node (ref "U1") (pin "45") (pinfunction "PB8_45") (pintype "bidirectional"))
      (node (ref "X4") (pin "15") (pinfunction "KL_15") (pintype "passive"))
    )
    (net (code "60") (name "TRIG") (class "Default")
      (node (ref "U1") (pin "29") (pinfunction "PA8_29") (pintype "bidirectional"))
      (node (ref "X4") (pin "31") (pinfunction "KL_31") (pintype "passive"))
    )
    (net (code "61") (name "TX1") (class "Default")
      (node (ref "R11") (pin "1") (pinfunction "1_1") (pintype "passive"))
      (node (ref "TP16") (pin "TP") (pinfunction "TP_TP") (pintype "input"))
      (node (ref "U1") (pin "30") (pinfunction "PA9_30") (pintype "bidirectional"))
      (node (ref "X4") (pin "32") (pinfunction "KL_32") (pintype "passive"))
    )
    (net (code "62") (name "USBDM") (class "Default")
      (node (ref "R15") (pin "1") (pinfunction "1_1") (pintype "passive"))
      (node (ref "TP19") (pin "TP") (pinfunction "TP_TP") (pintype "input"))
      (node (ref "U1") (pin "32") (pinfunction "PA11_32") (pintype "bidirectional"))
      (node (ref "X4") (pin "34") (pinfunction "KL_34") (pintype "passive"))
    )
    (net (code "63") (name "USBDP") (class "Default")
      (node (ref "R16") (pin "1") (pinfunction "1_1") (pintype "passive"))
      (node (ref "TP20") (pin "TP") (pinfunction "TP_TP") (pintype "input"))
      (node (ref "U1") (pin "33") (pinfunction "PA12_33") (pintype "bidirectional"))
      (node (ref "X4") (pin "35") (pinfunction "KL_35") (pintype "passive"))
    )
    (net (code "64") (name "V-MON") (class "Default")
      (node (ref "R7") (pin "1") (pinfunction "1_1") (pintype "passive"))
      (node (ref "R8") (pin "1") (pinfunction "1_1") (pintype "passive"))
      (node (ref "U1") (pin "16") (pinfunction "PA6_16") (pintype "bidirectional"))
      (node (ref "X4") (pin "29") (pinfunction "KL_29") (pintype "passive"))
    )
    (net (code "65") (name "VGEN") (class "Default")
      (node (ref "R6") (pin "1") (pinfunction "1_1") (pintype "passive"))
      (node (ref "U1") (pin "46") (pinfunction "PB9_46") (pintype "bidirectional"))
      (node (ref "X4") (pin "16") (pinfunction "KL_16") (pintype "passive"))
    )
    (net (code "66") (name "VSENSEL1") (class "Default")
      (node (ref "U1") (pin "12") (pinfunction "PA2_12") (pintype "bidirectional"))
      (node (ref "X4") (pin "24") (pinfunction "KL_24") (pintype "passive"))
    )
    (net (code "67") (name "VSENSEL2") (class "Default")
      (node (ref "U1") (pin "11") (pinfunction "PA1_11") (pintype "bidirectional"))
      (node (ref "X4") (pin "25") (pinfunction "KL_25") (pintype "passive"))
    )
    (net (code "68") (name "unconnected-(J1-Pad2)") (class "Default")
      (node (ref "J1") (pin "2") (pinfunction "2_2") (pintype "passive"))
    )
    (net (code "69") (name "unconnected-(JMP2-Pad3)") (class "Default")
      (node (ref "JMP2") (pin "3") (pinfunction "3_3") (pintype "passive"))
    )
    (net (code "70") (name "unconnected-(JP6-Pad10)") (class "Default")
      (node (ref "JP6") (pin "10") (pinfunction "10_10") (pintype "passive"))
    )
    (net (code "71") (name "unconnected-(JP6-Pad11)") (class "Default")
      (node (ref "JP6") (pin "11") (pinfunction "11_11") (pintype "passive"))
    )
    (net (code "72") (name "unconnected-(LCDHEADER-Pad1)") (class "Default")
      (node (ref "LCDHEADER") (pin "1") (pinfunction "1_1") (pintype "passive"))
    )
    (net (code "73") (name "unconnected-(LCDHEADER-Pad2)") (class "Default")
      (node (ref "LCDHEADER") (pin "2") (pinfunction "2_2") (pintype "passive"))
    )
    (net (code "74") (name "unconnected-(LCDHEADER-Pad3)") (class "Default")
      (node (ref "LCDHEADER") (pin "3") (pinfunction "3_3") (pintype "passive"))
    )
    (net (code "75") (name "unconnected-(LCDHEADER-Pad4)") (class "Default")
      (node (ref "LCDHEADER") (pin "4") (pinfunction "4_4") (pintype "passive"))
    )
    (net (code "76") (name "unconnected-(LCDHEADER-Pad12)") (class "Default")
      (node (ref "LCDHEADER") (pin "12") (pinfunction "12_12") (pintype "passive"))
    )
    (net (code "77") (name "unconnected-(LCDHEADER-Pad13)") (class "Default")
      (node (ref "LCDHEADER") (pin "13") (pinfunction "13_13") (pintype "passive"))
    )
    (net (code "78") (name "unconnected-(LCDHEADER-Pad14)") (class "Default")
      (node (ref "LCDHEADER") (pin "14") (pinfunction "14_14") (pintype "passive"))
    )
    (net (code "79") (name "unconnected-(LCDHEADER-Pad15)") (class "Default")
      (node (ref "LCDHEADER") (pin "15") (pinfunction "15_15") (pintype "passive"))
    )
    (net (code "80") (name "unconnected-(LCDHEADER-Pad22)") (class "Default")
      (node (ref "LCDHEADER") (pin "22") (pinfunction "22_22") (pintype "passive"))
    )
    (net (code "81") (name "unconnected-(LCDHEADER-Pad35)") (class "Default")
      (node (ref "LCDHEADER") (pin "35") (pinfunction "35_35") (pintype "passive"))
    )
    (net (code "82") (name "unconnected-(LCDHEADER-Pad36)") (class "Default")
      (node (ref "LCDHEADER") (pin "36") (pinfunction "36_36") (pintype "passive"))
    )
    (net (code "83") (name "unconnected-(LCDHEADER-Pad37)") (class "Default")
      (node (ref "LCDHEADER") (pin "37") (pinfunction "37_37") (pintype "passive"))
    )
    (net (code "84") (name "unconnected-(LCDHEADER-Pad38)") (class "Default")
      (node (ref "LCDHEADER") (pin "38") (pinfunction "38_38") (pintype "passive"))
    )
    (net (code "85") (name "unconnected-(LCDHEADER-Pad39)") (class "Default")
      (node (ref "LCDHEADER") (pin "39") (pinfunction "39_39") (pintype "passive"))
    )
    (net (code "86") (name "unconnected-(LCDHEADER-Pad40)") (class "Default")
      (node (ref "LCDHEADER") (pin "40") (pinfunction "40_40") (pintype "passive"))
    )
    (net (code "87") (name "unconnected-(X3-Pad4)") (class "Default")
      (node (ref "X3") (pin "4") (pinfunction "4_4") (pintype "passive"))
    )
  )
)
